# schematic.net
KiCad netlist of a schematic drawn in EAGLE
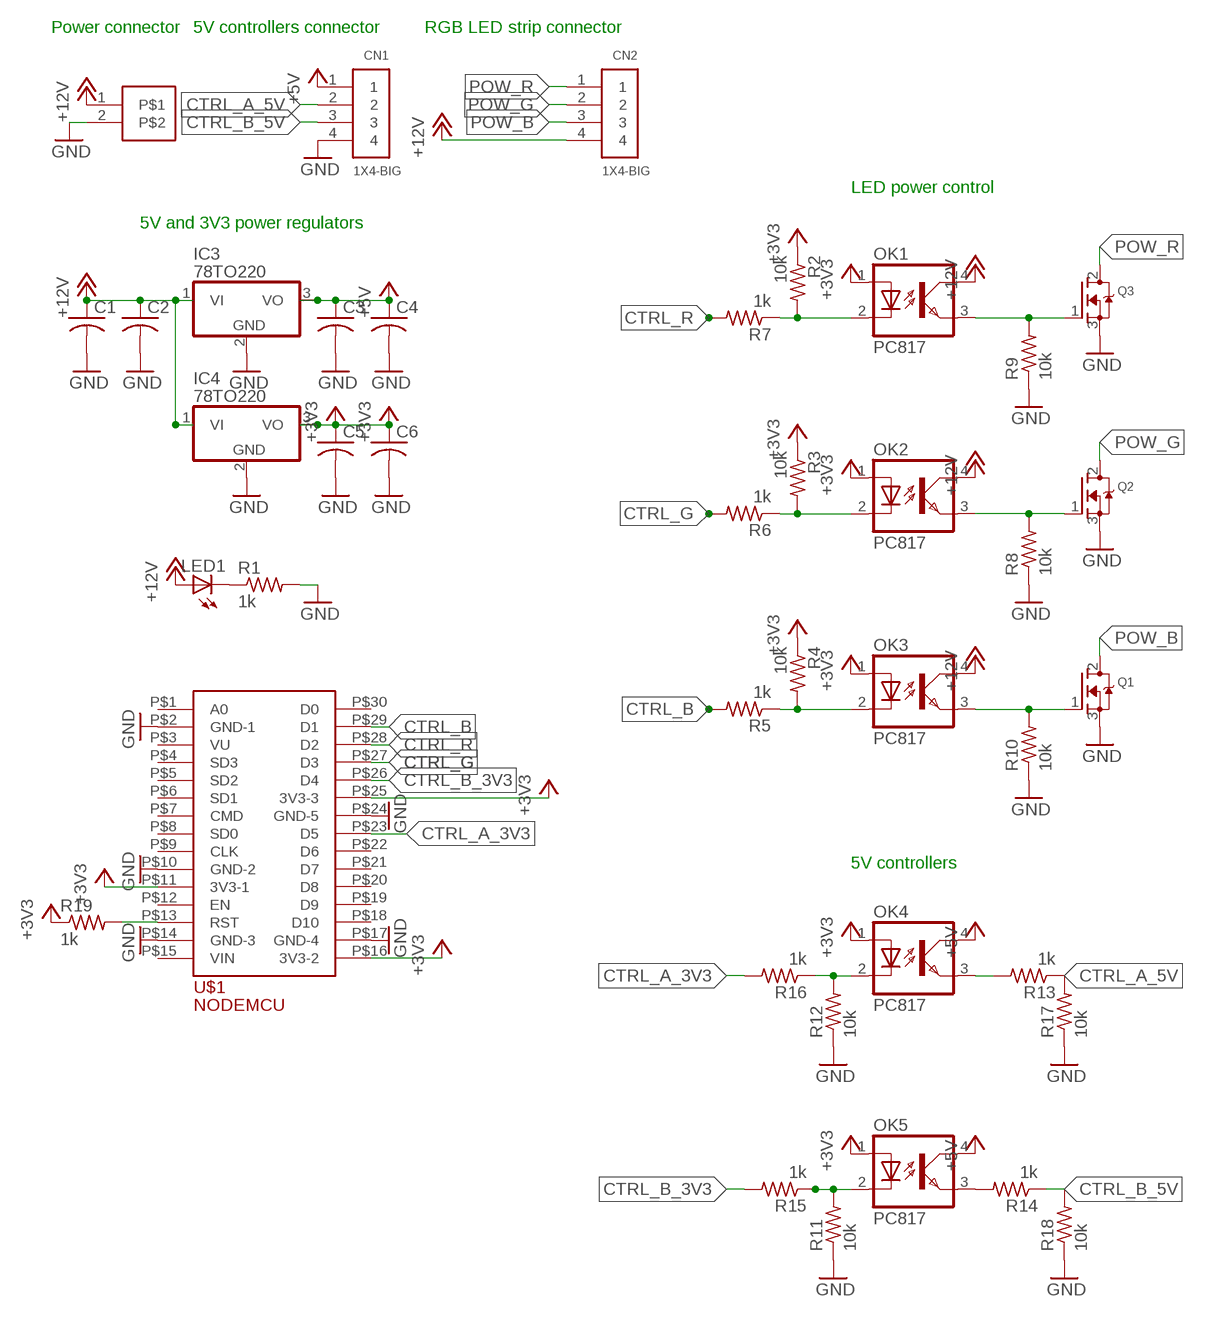
[diagram p0: schematic, sheet 1]

(export (version "E")
  (design (tool "Eeschema 10.0.6"))
  (components
    (comp (ref "C1")
      (value "C-USC0805")
      (footprint "eagle-import:C0805")
      (libsource (lib "eagle-import") (part "C-USC0805"))
    )
    (comp (ref "C2")
      (value "C-USC0805")
      (footprint "eagle-import:C0805")
      (libsource (lib "eagle-import") (part "C-USC0805"))
    )
    (comp (ref "C3")
      (value "C-USC0805")
      (footprint "eagle-import:C0805")
      (libsource (lib "eagle-import") (part "C-USC0805"))
    )
    (comp (ref "C4")
      (value "C-USC0805")
      (footprint "eagle-import:C0805")
      (libsource (lib "eagle-import") (part "C-USC0805"))
    )
    (comp (ref "C5")
      (value "C-USC0805")
      (footprint "eagle-import:C0805")
      (libsource (lib "eagle-import") (part "C-USC0805"))
    )
    (comp (ref "C6")
      (value "C-USC0805")
      (footprint "eagle-import:C0805")
      (libsource (lib "eagle-import") (part "C-USC0805"))
    )
    (comp (ref "CN1")
      (value "1X4-BIG")
      (footprint "eagle-import:1X04-BIG")
      (libsource (lib "eagle-import") (part "1X4-BIG"))
    )
    (comp (ref "CN2")
      (value "1X4-BIG")
      (footprint "eagle-import:1X04-BIG")
      (libsource (lib "eagle-import") (part "1X4-BIG"))
    )
    (comp (ref "IC3")
      (value "78TO220")
      (footprint "eagle-import:TO220V")
      (libsource (lib "eagle-import") (part "78TO220"))
    )
    (comp (ref "IC4")
      (value "78TO220")
      (footprint "eagle-import:TO220V")
      (libsource (lib "eagle-import") (part "78TO220"))
    )
    (comp (ref "LED1")
      (value "LEDSMT1206")
      (footprint "eagle-import:1206")
      (libsource (lib "eagle-import") (part "LEDSMT1206"))
    )
    (comp (ref "OK1")
      (value "PC817")
      (footprint "eagle-import:DIL04")
      (fields (field (name "MPN") "PC817X4J000F"))
      (libsource (lib "eagle-import") (part "PC817"))
    )
    (comp (ref "OK2")
      (value "PC817")
      (footprint "eagle-import:DIL04")
      (fields (field (name "MPN") "PC817X4J000F"))
      (libsource (lib "eagle-import") (part "PC817"))
    )
    (comp (ref "OK3")
      (value "PC817")
      (footprint "eagle-import:DIL04")
      (fields (field (name "MPN") "PC817X4J000F"))
      (libsource (lib "eagle-import") (part "PC817"))
    )
    (comp (ref "OK4")
      (value "PC817")
      (footprint "eagle-import:DIL04")
      (fields (field (name "MPN") "PC817X4J000F"))
      (libsource (lib "eagle-import") (part "PC817"))
    )
    (comp (ref "OK5")
      (value "PC817")
      (footprint "eagle-import:DIL04")
      (fields (field (name "MPN") "PC817X4J000F"))
      (libsource (lib "eagle-import") (part "PC817"))
    )
    (comp (ref "Q1")
      (value "MOSFET-NGDS_TO220V")
      (footprint "eagle-import:TO220V")
      (libsource (lib "eagle-import") (part "MOSFET-NGDS_TO220V"))
    )
    (comp (ref "Q2")
      (value "MOSFET-NGDS_TO220V")
      (footprint "eagle-import:TO220V")
      (libsource (lib "eagle-import") (part "MOSFET-NGDS_TO220V"))
    )
    (comp (ref "Q3")
      (value "MOSFET-NGDS_TO220V")
      (footprint "eagle-import:TO220V")
      (libsource (lib "eagle-import") (part "MOSFET-NGDS_TO220V"))
    )
    (comp (ref "R1")
      (value "1k")
      (footprint "eagle-import:M0805")
      (libsource (lib "eagle-import") (part "R-US_M0805"))
    )
    (comp (ref "R2")
      (value "10k")
      (footprint "eagle-import:R0805")
      (libsource (lib "eagle-import") (part "R-US_R0805"))
    )
    (comp (ref "R3")
      (value "10k")
      (footprint "eagle-import:R0805")
      (libsource (lib "eagle-import") (part "R-US_R0805"))
    )
    (comp (ref "R4")
      (value "10k")
      (footprint "eagle-import:R0805")
      (libsource (lib "eagle-import") (part "R-US_R0805"))
    )
    (comp (ref "R5")
      (value "1k")
      (footprint "eagle-import:R0805")
      (libsource (lib "eagle-import") (part "R-US_R0805"))
    )
    (comp (ref "R6")
      (value "1k")
      (footprint "eagle-import:R0805")
      (libsource (lib "eagle-import") (part "R-US_R0805"))
    )
    (comp (ref "R7")
      (value "1k")
      (footprint "eagle-import:R0805")
      (libsource (lib "eagle-import") (part "R-US_R0805"))
    )
    (comp (ref "R8")
      (value "10k")
      (footprint "eagle-import:R0805")
      (libsource (lib "eagle-import") (part "R-US_R0805"))
    )
    (comp (ref "R9")
      (value "10k")
      (footprint "eagle-import:R0805")
      (libsource (lib "eagle-import") (part "R-US_R0805"))
    )
    (comp (ref "R10")
      (value "10k")
      (footprint "eagle-import:R0805")
      (libsource (lib "eagle-import") (part "R-US_R0805"))
    )
    (comp (ref "R11")
      (value "10k")
      (footprint "eagle-import:R0805")
      (libsource (lib "eagle-import") (part "R-US_R0805"))
    )
    (comp (ref "R12")
      (value "10k")
      (footprint "eagle-import:R0805")
      (libsource (lib "eagle-import") (part "R-US_R0805"))
    )
    (comp (ref "R13")
      (value "1k")
      (footprint "eagle-import:R0805")
      (libsource (lib "eagle-import") (part "R-US_R0805"))
    )
    (comp (ref "R14")
      (value "1k")
      (footprint "eagle-import:R0805")
      (libsource (lib "eagle-import") (part "R-US_R0805"))
    )
    (comp (ref "R15")
      (value "1k")
      (footprint "eagle-import:R0805")
      (libsource (lib "eagle-import") (part "R-US_R0805"))
    )
    (comp (ref "R16")
      (value "1k")
      (footprint "eagle-import:R0805")
      (libsource (lib "eagle-import") (part "R-US_R0805"))
    )
    (comp (ref "R17")
      (value "10k")
      (footprint "eagle-import:R0805")
      (libsource (lib "eagle-import") (part "R-US_R0805"))
    )
    (comp (ref "R18")
      (value "10k")
      (footprint "eagle-import:R0805")
      (libsource (lib "eagle-import") (part "R-US_R0805"))
    )
    (comp (ref "R19")
      (value "1k")
      (footprint "eagle-import:M0805")
      (libsource (lib "eagle-import") (part "R-US_M0805"))
    )
    (comp (ref "U$1")
      (value "ESP8266")
      (footprint "eagle-import:ESP8266-NODEMCU")
      (libsource (lib "eagle-import") (part "ESP8266"))
    )
    (comp (ref "U$2")
      (value "HEADER-2X1")
      (footprint "eagle-import:HEADER-2X1")
      (libsource (lib "eagle-import") (part "HEADER-2X1"))
    )
  )
  (nets
    (net (code "1") (name "+3V3") (class "Default")
      (node (ref "C5") (pin "1") (pinfunction "1_1") (pintype "passive"))
      (node (ref "C6") (pin "1") (pinfunction "1_1") (pintype "passive"))
      (node (ref "IC4") (pin "3") (pinfunction "VO_3") (pintype "passive"))
      (node (ref "OK1") (pin "1") (pinfunction "A_1") (pintype "passive"))
      (node (ref "OK2") (pin "1") (pinfunction "A_1") (pintype "passive"))
      (node (ref "OK3") (pin "1") (pinfunction "A_1") (pintype "passive"))
      (node (ref "OK4") (pin "1") (pinfunction "A_1") (pintype "passive"))
      (node (ref "OK5") (pin "1") (pinfunction "A_1") (pintype "passive"))
      (node (ref "R19") (pin "1") (pinfunction "1_1") (pintype "passive"))
      (node (ref "R2") (pin "1") (pinfunction "1_1") (pintype "passive"))
      (node (ref "R3") (pin "1") (pinfunction "1_1") (pintype "passive"))
      (node (ref "R4") (pin "1") (pinfunction "1_1") (pintype "passive"))
      (node (ref "U$1") (pin "P$11") (pinfunction "3V3-1_P$11") (pintype "bidirectional"))
      (node (ref "U$1") (pin "P$16") (pinfunction "3V3-2_P$16") (pintype "bidirectional"))
      (node (ref "U$1") (pin "P$25") (pinfunction "3V3-3_P$25") (pintype "bidirectional"))
    )
    (net (code "2") (name "+5V") (class "Default")
      (node (ref "C3") (pin "1") (pinfunction "1_1") (pintype "passive"))
      (node (ref "C4") (pin "1") (pinfunction "1_1") (pintype "passive"))
      (node (ref "CN1") (pin "1") (pinfunction "1_1") (pintype "bidirectional"))
      (node (ref "IC3") (pin "3") (pinfunction "VO_3") (pintype "passive"))
      (node (ref "OK4") (pin "4") (pinfunction "COL_4") (pintype "passive"))
      (node (ref "OK5") (pin "4") (pinfunction "COL_4") (pintype "passive"))
    )
    (net (code "3") (name "+12V") (class "Default")
      (node (ref "C1") (pin "1") (pinfunction "1_1") (pintype "passive"))
      (node (ref "C2") (pin "1") (pinfunction "1_1") (pintype "passive"))
      (node (ref "CN2") (pin "4") (pinfunction "4_4") (pintype "bidirectional"))
      (node (ref "IC3") (pin "1") (pinfunction "VI_1") (pintype "input"))
      (node (ref "IC4") (pin "1") (pinfunction "VI_1") (pintype "input"))
      (node (ref "LED1") (pin "A") (pinfunction "A_A") (pintype "passive"))
      (node (ref "OK1") (pin "4") (pinfunction "COL_4") (pintype "passive"))
      (node (ref "OK2") (pin "4") (pinfunction "COL_4") (pintype "passive"))
      (node (ref "OK3") (pin "4") (pinfunction "COL_4") (pintype "passive"))
      (node (ref "U$2") (pin "1") (pinfunction "P$1_1") (pintype "bidirectional"))
    )
    (net (code "4") (name "CTRL_A_3V3") (class "Default")
      (node (ref "R16") (pin "2") (pinfunction "2_2") (pintype "passive"))
      (node (ref "U$1") (pin "P$23") (pinfunction "D5_P$23") (pintype "bidirectional"))
    )
    (net (code "5") (name "CTRL_A_5V") (class "Default")
      (node (ref "CN1") (pin "2") (pinfunction "2_2") (pintype "bidirectional"))
      (node (ref "R13") (pin "1") (pinfunction "1_1") (pintype "passive"))
      (node (ref "R17") (pin "2") (pinfunction "2_2") (pintype "passive"))
    )
    (net (code "6") (name "CTRL_B") (class "Default")
      (node (ref "R5") (pin "2") (pinfunction "2_2") (pintype "passive"))
      (node (ref "U$1") (pin "P$29") (pinfunction "D1_P$29") (pintype "bidirectional"))
    )
    (net (code "7") (name "CTRL_B_3V3") (class "Default")
      (node (ref "R15") (pin "2") (pinfunction "2_2") (pintype "passive"))
      (node (ref "U$1") (pin "P$26") (pinfunction "D4_P$26") (pintype "bidirectional"))
    )
    (net (code "8") (name "CTRL_B_5V") (class "Default")
      (node (ref "CN1") (pin "3") (pinfunction "3_3") (pintype "bidirectional"))
      (node (ref "R14") (pin "1") (pinfunction "1_1") (pintype "passive"))
      (node (ref "R18") (pin "2") (pinfunction "2_2") (pintype "passive"))
    )
    (net (code "9") (name "CTRL_G") (class "Default")
      (node (ref "R6") (pin "2") (pinfunction "2_2") (pintype "passive"))
      (node (ref "U$1") (pin "P$27") (pinfunction "D3_P$27") (pintype "bidirectional"))
    )
    (net (code "10") (name "CTRL_R") (class "Default")
      (node (ref "R7") (pin "2") (pinfunction "2_2") (pintype "passive"))
      (node (ref "U$1") (pin "P$28") (pinfunction "D2_P$28") (pintype "bidirectional"))
    )
    (net (code "11") (name "GND") (class "Default")
      (node (ref "C1") (pin "2") (pinfunction "2_2") (pintype "passive"))
      (node (ref "C2") (pin "2") (pinfunction "2_2") (pintype "passive"))
      (node (ref "C3") (pin "2") (pinfunction "2_2") (pintype "passive"))
      (node (ref "C4") (pin "2") (pinfunction "2_2") (pintype "passive"))
      (node (ref "C5") (pin "2") (pinfunction "2_2") (pintype "passive"))
      (node (ref "C6") (pin "2") (pinfunction "2_2") (pintype "passive"))
      (node (ref "CN1") (pin "4") (pinfunction "4_4") (pintype "bidirectional"))
      (node (ref "IC3") (pin "2") (pinfunction "GND_2") (pintype "passive"))
      (node (ref "IC4") (pin "2") (pinfunction "GND_2") (pintype "passive"))
      (node (ref "Q1") (pin "3") (pinfunction "S_3") (pintype "bidirectional"))
      (node (ref "Q2") (pin "3") (pinfunction "S_3") (pintype "bidirectional"))
      (node (ref "Q3") (pin "3") (pinfunction "S_3") (pintype "bidirectional"))
      (node (ref "R1") (pin "2") (pinfunction "2_2") (pintype "passive"))
      (node (ref "R10") (pin "1") (pinfunction "1_1") (pintype "passive"))
      (node (ref "R11") (pin "1") (pinfunction "1_1") (pintype "passive"))
      (node (ref "R12") (pin "1") (pinfunction "1_1") (pintype "passive"))
      (node (ref "R17") (pin "1") (pinfunction "1_1") (pintype "passive"))
      (node (ref "R18") (pin "1") (pinfunction "1_1") (pintype "passive"))
      (node (ref "R8") (pin "1") (pinfunction "1_1") (pintype "passive"))
      (node (ref "R9") (pin "1") (pinfunction "1_1") (pintype "passive"))
      (node (ref "U$1") (pin "P$10") (pinfunction "GND-2_P$10") (pintype "bidirectional"))
      (node (ref "U$1") (pin "P$14") (pinfunction "GND-3_P$14") (pintype "bidirectional"))
      (node (ref "U$1") (pin "P$17") (pinfunction "GND-4_P$17") (pintype "bidirectional"))
      (node (ref "U$1") (pin "P$2") (pinfunction "GND-1_P$2") (pintype "bidirectional"))
      (node (ref "U$1") (pin "P$24") (pinfunction "GND-5_P$24") (pintype "bidirectional"))
      (node (ref "U$2") (pin "2") (pinfunction "P$2_2") (pintype "bidirectional"))
    )
    (net (code "12") (name "Net-(LED1-PadC)") (class "Default")
      (node (ref "LED1") (pin "C") (pinfunction "C_C") (pintype "passive"))
      (node (ref "R1") (pin "1") (pinfunction "1_1") (pintype "passive"))
    )
    (net (code "13") (name "Net-(OK1-C)") (class "Default")
      (node (ref "OK1") (pin "2") (pinfunction "C_2") (pintype "passive"))
      (node (ref "R2") (pin "2") (pinfunction "2_2") (pintype "passive"))
      (node (ref "R7") (pin "1") (pinfunction "1_1") (pintype "passive"))
    )
    (net (code "14") (name "Net-(OK1-EMIT)") (class "Default")
      (node (ref "OK1") (pin "3") (pinfunction "EMIT_3") (pintype "passive"))
      (node (ref "Q3") (pin "1") (pinfunction "G_1") (pintype "bidirectional"))
      (node (ref "R9") (pin "2") (pinfunction "2_2") (pintype "passive"))
    )
    (net (code "15") (name "Net-(OK2-C)") (class "Default")
      (node (ref "OK2") (pin "2") (pinfunction "C_2") (pintype "passive"))
      (node (ref "R3") (pin "2") (pinfunction "2_2") (pintype "passive"))
      (node (ref "R6") (pin "1") (pinfunction "1_1") (pintype "passive"))
    )
    (net (code "16") (name "Net-(OK2-EMIT)") (class "Default")
      (node (ref "OK2") (pin "3") (pinfunction "EMIT_3") (pintype "passive"))
      (node (ref "Q2") (pin "1") (pinfunction "G_1") (pintype "bidirectional"))
      (node (ref "R8") (pin "2") (pinfunction "2_2") (pintype "passive"))
    )
    (net (code "17") (name "Net-(OK3-C)") (class "Default")
      (node (ref "OK3") (pin "2") (pinfunction "C_2") (pintype "passive"))
      (node (ref "R4") (pin "2") (pinfunction "2_2") (pintype "passive"))
      (node (ref "R5") (pin "1") (pinfunction "1_1") (pintype "passive"))
    )
    (net (code "18") (name "Net-(OK3-EMIT)") (class "Default")
      (node (ref "OK3") (pin "3") (pinfunction "EMIT_3") (pintype "passive"))
      (node (ref "Q1") (pin "1") (pinfunction "G_1") (pintype "bidirectional"))
      (node (ref "R10") (pin "2") (pinfunction "2_2") (pintype "passive"))
    )
    (net (code "19") (name "Net-(OK4-C)") (class "Default")
      (node (ref "OK4") (pin "2") (pinfunction "C_2") (pintype "passive"))
      (node (ref "R12") (pin "2") (pinfunction "2_2") (pintype "passive"))
      (node (ref "R16") (pin "1") (pinfunction "1_1") (pintype "passive"))
    )
    (net (code "20") (name "Net-(OK4-EMIT)") (class "Default")
      (node (ref "OK4") (pin "3") (pinfunction "EMIT_3") (pintype "passive"))
      (node (ref "R13") (pin "2") (pinfunction "2_2") (pintype "passive"))
    )
    (net (code "21") (name "Net-(OK5-C)") (class "Default")
      (node (ref "OK5") (pin "2") (pinfunction "C_2") (pintype "passive"))
      (node (ref "R11") (pin "2") (pinfunction "2_2") (pintype "passive"))
      (node (ref "R15") (pin "1") (pinfunction "1_1") (pintype "passive"))
    )
    (net (code "22") (name "Net-(OK5-EMIT)") (class "Default")
      (node (ref "OK5") (pin "3") (pinfunction "EMIT_3") (pintype "passive"))
      (node (ref "R14") (pin "2") (pinfunction "2_2") (pintype "passive"))
    )
    (net (code "23") (name "Net-(U$1-RST)") (class "Default")
      (node (ref "R19") (pin "2") (pinfunction "2_2") (pintype "passive"))
      (node (ref "U$1") (pin "P$13") (pinfunction "RST_P$13") (pintype "bidirectional"))
    )
    (net (code "24") (name "POW_B") (class "Default")
      (node (ref "CN2") (pin "3") (pinfunction "3_3") (pintype "bidirectional"))
      (node (ref "Q1") (pin "2") (pinfunction "D_2") (pintype "bidirectional"))
    )
    (net (code "25") (name "POW_G") (class "Default")
      (node (ref "CN2") (pin "2") (pinfunction "2_2") (pintype "bidirectional"))
      (node (ref "Q2") (pin "2") (pinfunction "D_2") (pintype "bidirectional"))
    )
    (net (code "26") (name "POW_R") (class "Default")
      (node (ref "CN2") (pin "1") (pinfunction "1_1") (pintype "bidirectional"))
      (node (ref "Q3") (pin "2") (pinfunction "D_2") (pintype "bidirectional"))
    )
    (net (code "27") (name "unconnected-(U$1-A0-PadP$1)") (class "Default")
      (node (ref "U$1") (pin "P$1") (pinfunction "A0_P$1") (pintype "bidirectional"))
    )
    (net (code "28") (name "unconnected-(U$1-CLK-PadP$9)") (class "Default")
      (node (ref "U$1") (pin "P$9") (pinfunction "CLK_P$9") (pintype "bidirectional"))
    )
    (net (code "29") (name "unconnected-(U$1-CMD-PadP$7)") (class "Default")
      (node (ref "U$1") (pin "P$7") (pinfunction "CMD_P$7") (pintype "bidirectional"))
    )
    (net (code "30") (name "unconnected-(U$1-D0-PadP$30)") (class "Default")
      (node (ref "U$1") (pin "P$30") (pinfunction "D0_P$30") (pintype "bidirectional"))
    )
    (net (code "31") (name "unconnected-(U$1-D6-PadP$22)") (class "Default")
      (node (ref "U$1") (pin "P$22") (pinfunction "D6_P$22") (pintype "bidirectional"))
    )
    (net (code "32") (name "unconnected-(U$1-D7-PadP$21)") (class "Default")
      (node (ref "U$1") (pin "P$21") (pinfunction "D7_P$21") (pintype "bidirectional"))
    )
    (net (code "33") (name "unconnected-(U$1-D8-PadP$20)") (class "Default")
      (node (ref "U$1") (pin "P$20") (pinfunction "D8_P$20") (pintype "bidirectional"))
    )
    (net (code "34") (name "unconnected-(U$1-D9-PadP$19)") (class "Default")
      (node (ref "U$1") (pin "P$19") (pinfunction "D9_P$19") (pintype "bidirectional"))
    )
    (net (code "35") (name "unconnected-(U$1-D10-PadP$18)") (class "Default")
      (node (ref "U$1") (pin "P$18") (pinfunction "D10_P$18") (pintype "bidirectional"))
    )
    (net (code "36") (name "unconnected-(U$1-EN-PadP$12)") (class "Default")
      (node (ref "U$1") (pin "P$12") (pinfunction "EN_P$12") (pintype "bidirectional"))
    )
    (net (code "37") (name "unconnected-(U$1-SD0-PadP$8)") (class "Default")
      (node (ref "U$1") (pin "P$8") (pinfunction "SD0_P$8") (pintype "bidirectional"))
    )
    (net (code "38") (name "unconnected-(U$1-SD1-PadP$6)") (class "Default")
      (node (ref "U$1") (pin "P$6") (pinfunction "SD1_P$6") (pintype "bidirectional"))
    )
    (net (code "39") (name "unconnected-(U$1-SD2-PadP$5)") (class "Default")
      (node (ref "U$1") (pin "P$5") (pinfunction "SD2_P$5") (pintype "bidirectional"))
    )
    (net (code "40") (name "unconnected-(U$1-SD3-PadP$4)") (class "Default")
      (node (ref "U$1") (pin "P$4") (pinfunction "SD3_P$4") (pintype "bidirectional"))
    )
    (net (code "41") (name "unconnected-(U$1-VIN-PadP$15)") (class "Default")
      (node (ref "U$1") (pin "P$15") (pinfunction "VIN_P$15") (pintype "bidirectional"))
    )
    (net (code "42") (name "unconnected-(U$1-VU-PadP$3)") (class "Default")
      (node (ref "U$1") (pin "P$3") (pinfunction "VU_P$3") (pintype "bidirectional"))
    )
  )
)
